# Macropad.net
KiCad netlist of a schematic drawn in EAGLE
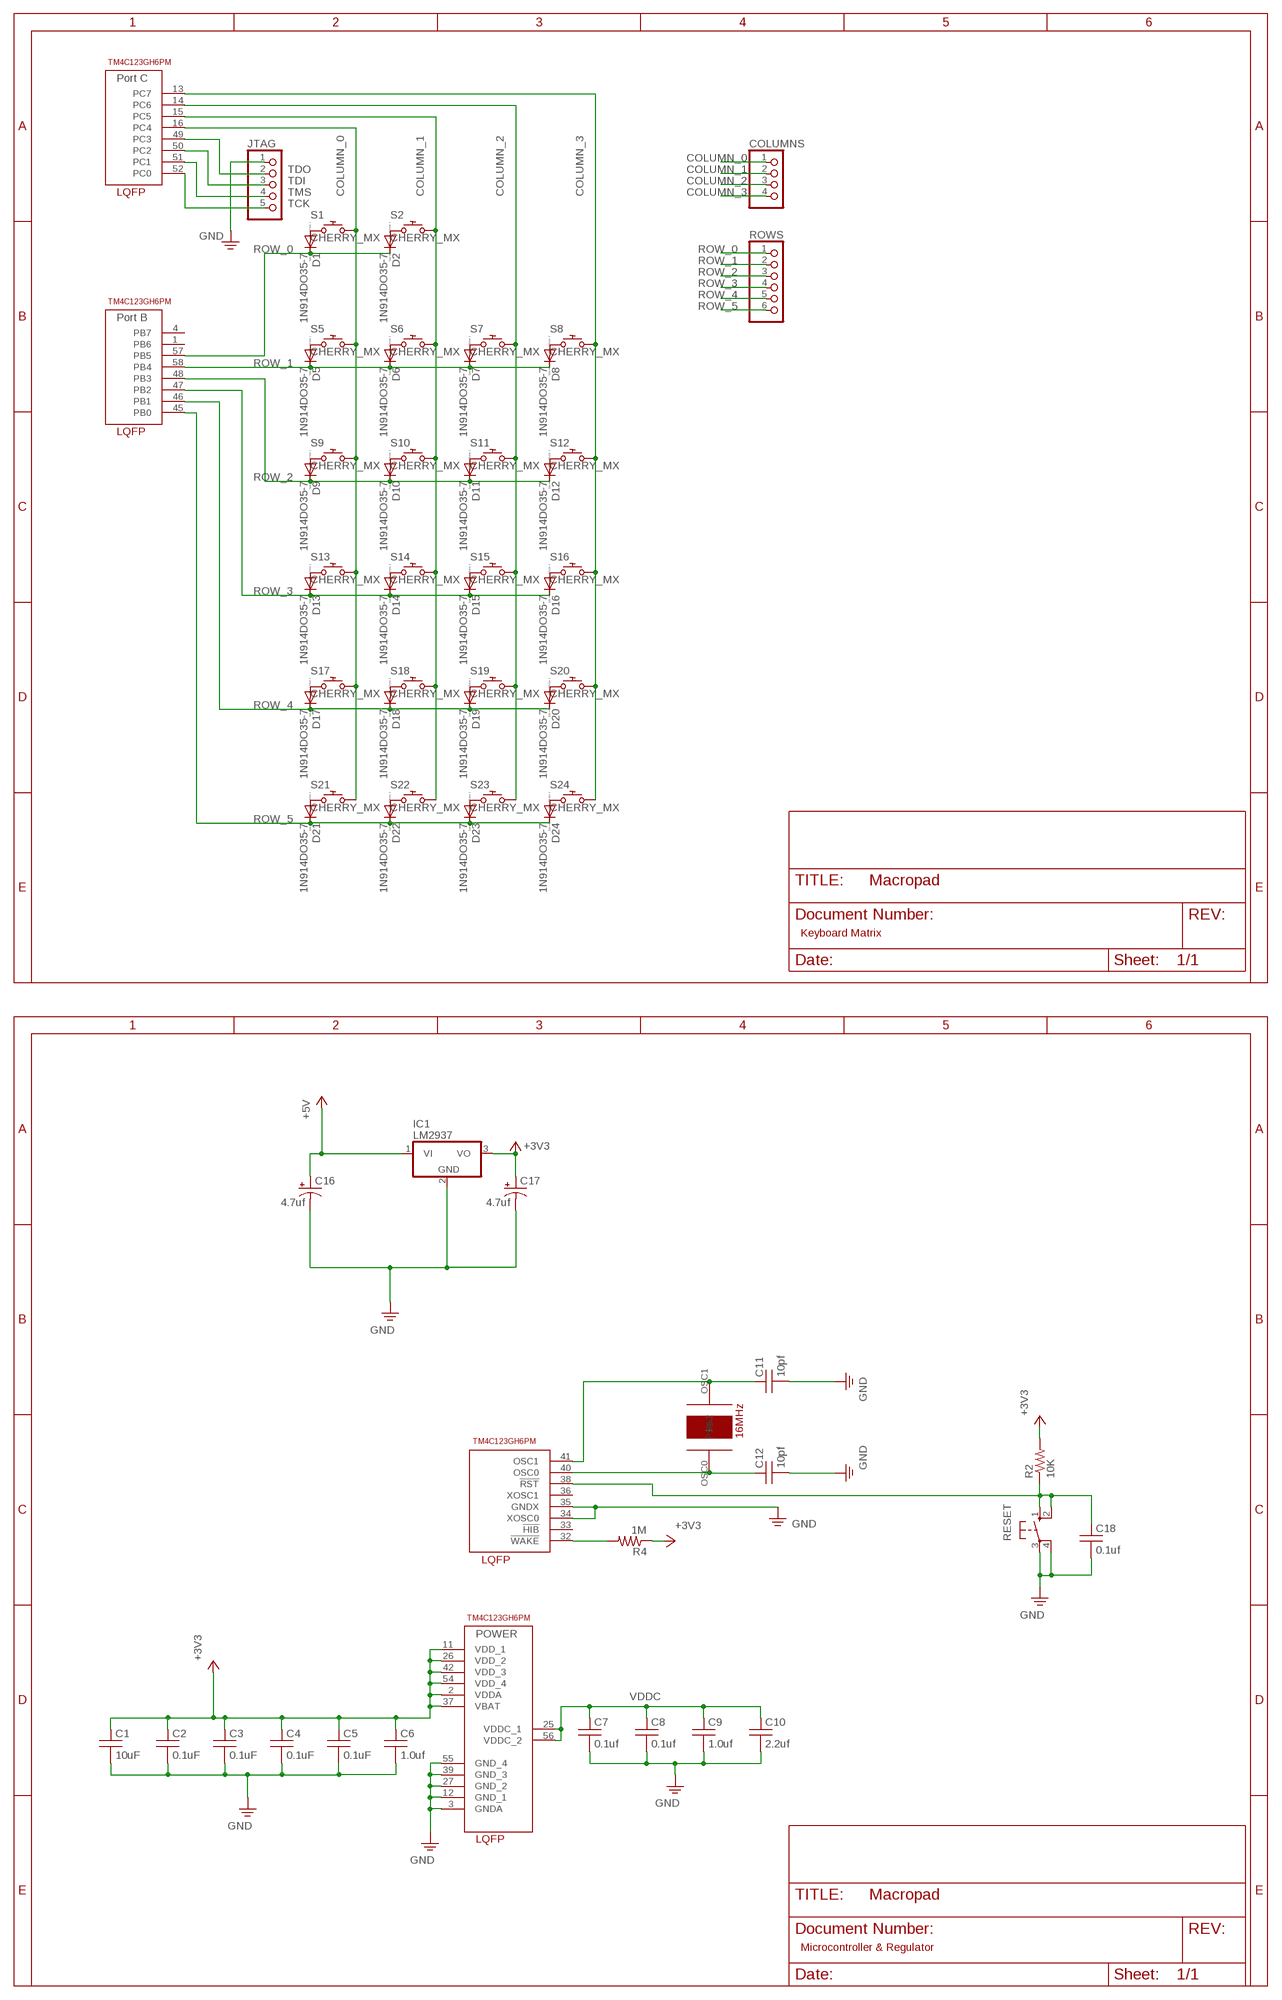
[diagram p0: schematic, sheet 1, part 1 of 2]
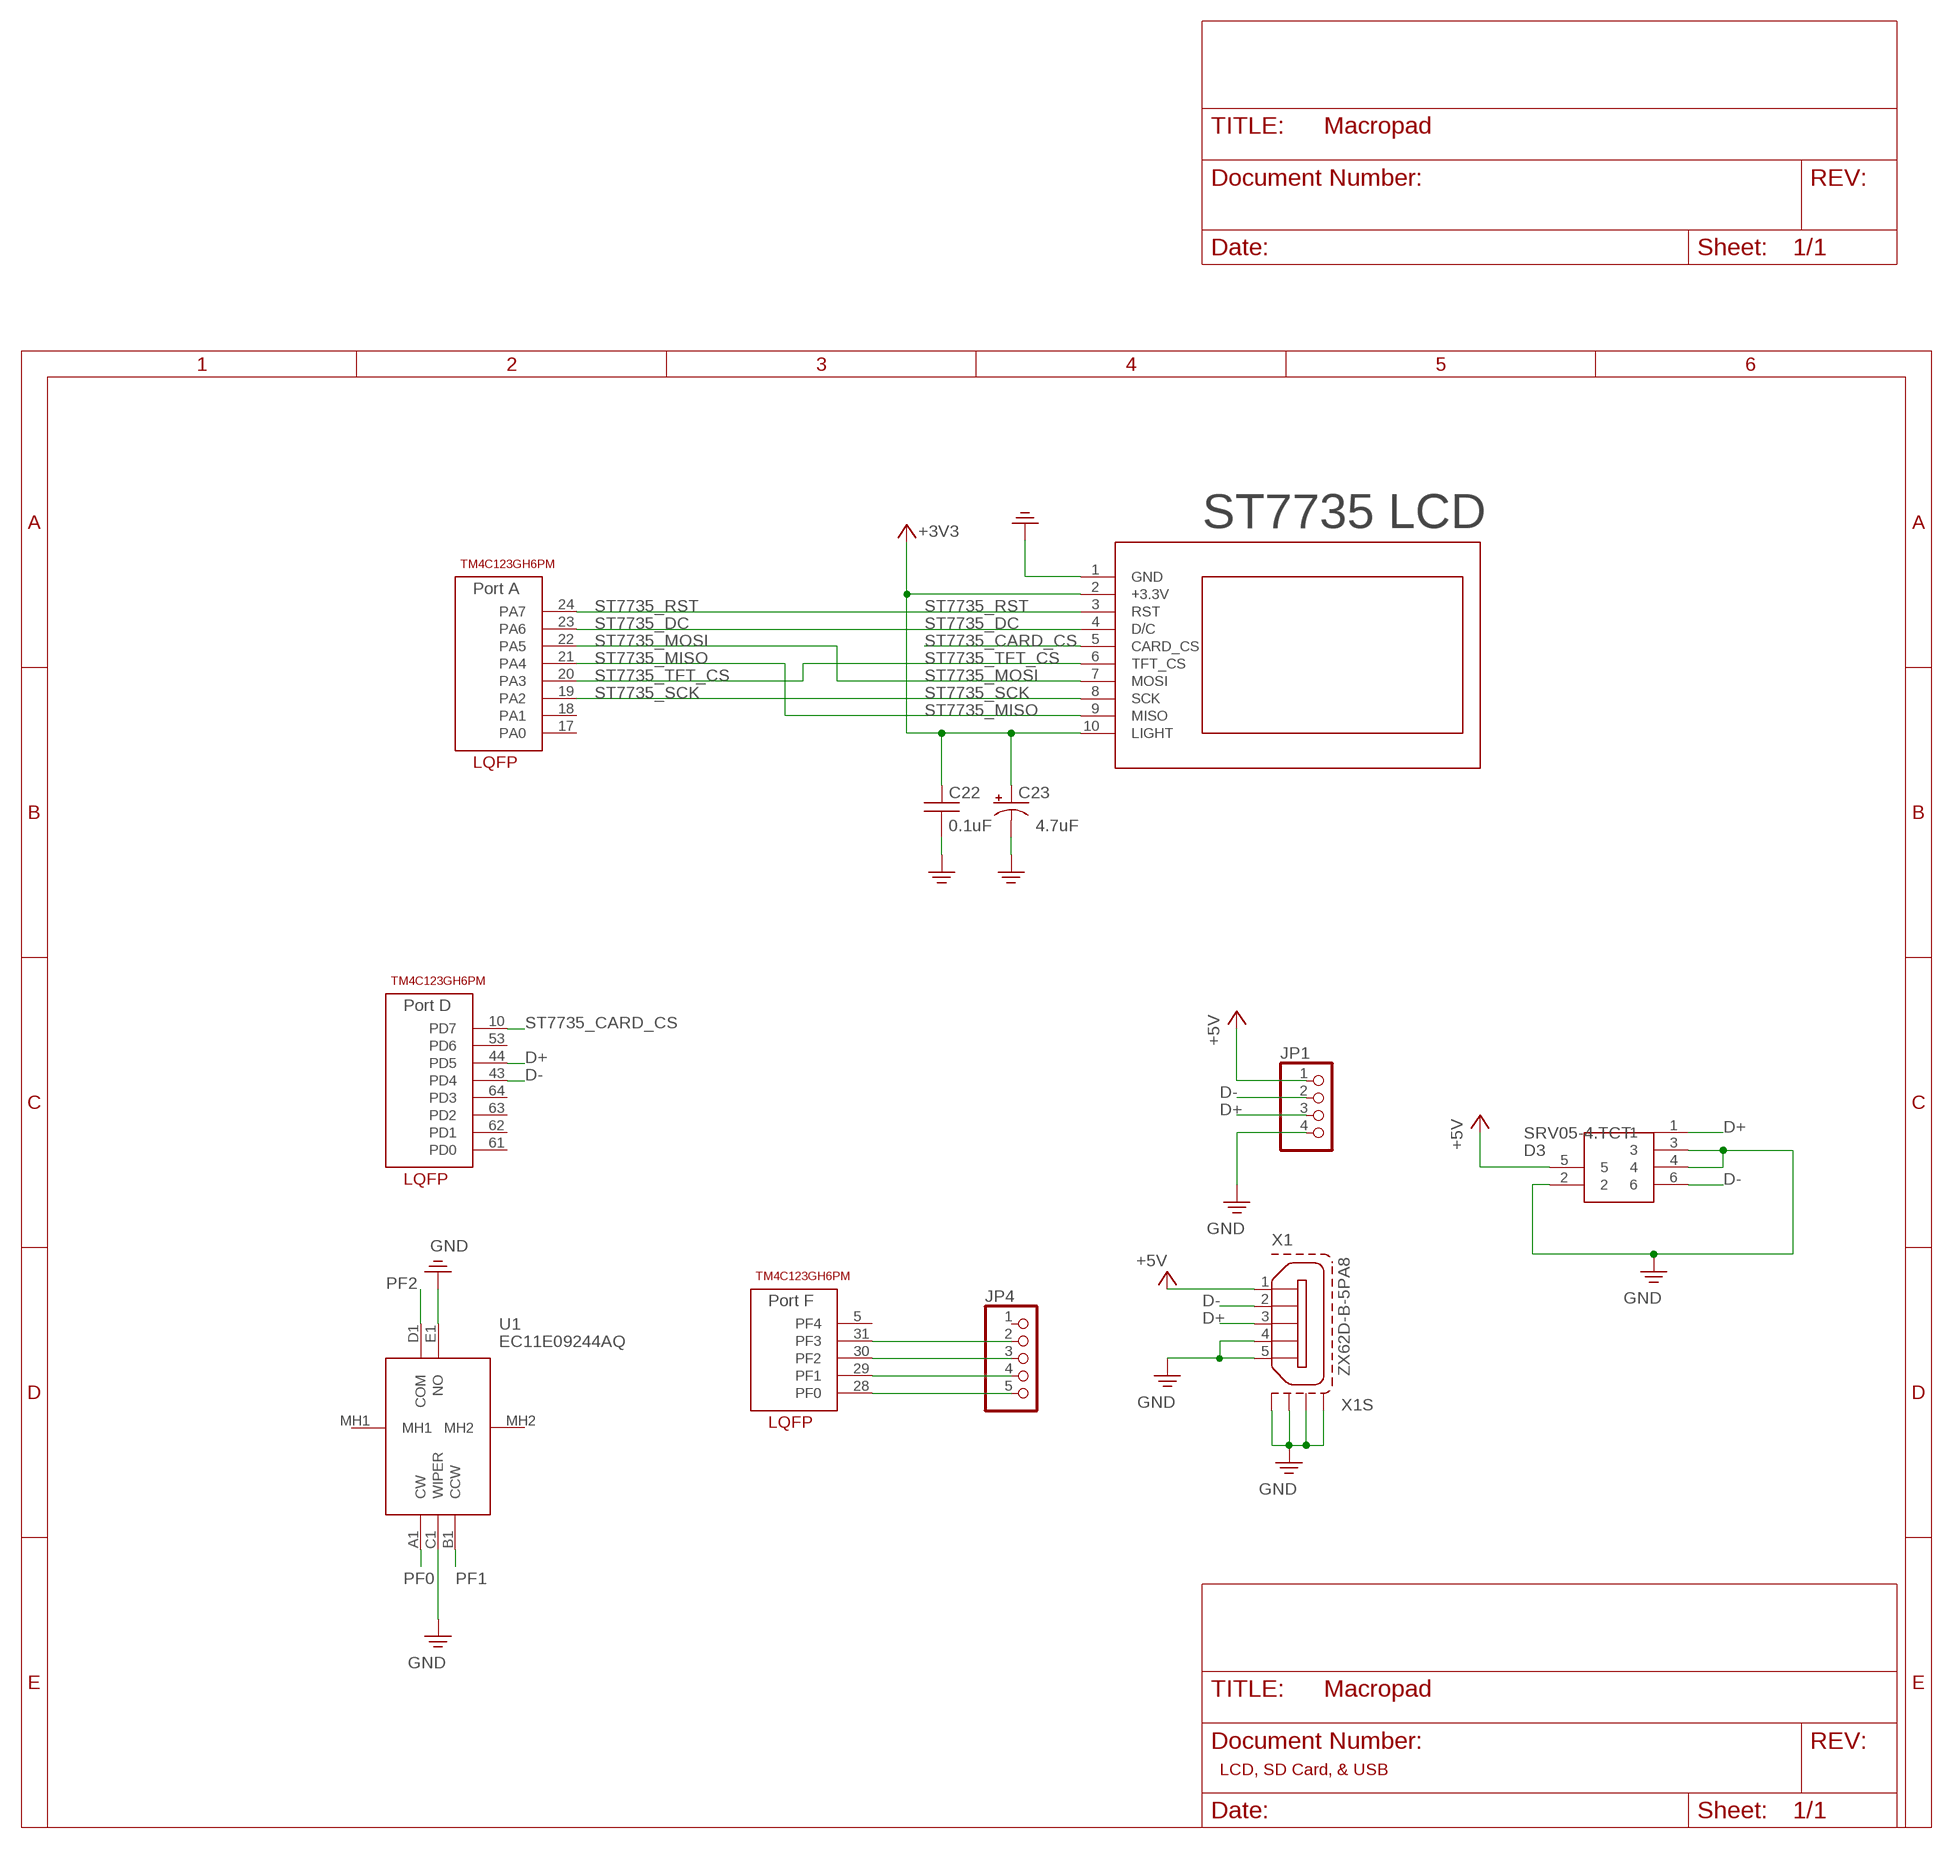
[diagram p1: schematic, sheet 1, part 2 of 2]

(export (version "E")
  (design (tool "Eeschema 10.0.6"))
  (components
    (comp (ref "C1")
      (value "10uF")
      (footprint "eagle-import:CAP100MIL")
      (libsource (lib "eagle-import") (part "CAPACITOR025-024X044"))
    )
    (comp (ref "C2")
      (value "0.1uF")
      (footprint "eagle-import:CAP100MIL")
      (libsource (lib "eagle-import") (part "CAPACITOR025-024X044"))
    )
    (comp (ref "C3")
      (value "0.1uF")
      (footprint "eagle-import:CAP100MIL")
      (libsource (lib "eagle-import") (part "CAPACITOR025-024X044"))
    )
    (comp (ref "C4")
      (value "0.1uF")
      (footprint "eagle-import:CAP100MIL")
      (libsource (lib "eagle-import") (part "CAPACITOR025-024X044"))
    )
    (comp (ref "C5")
      (value "0.1uF")
      (footprint "eagle-import:CAP100MIL")
      (libsource (lib "eagle-import") (part "CAPACITOR025-024X044"))
    )
    (comp (ref "C6")
      (value "1.0uf")
      (footprint "eagle-import:CAP100MIL")
      (libsource (lib "eagle-import") (part "CAPACITOR025-024X044"))
    )
    (comp (ref "C7")
      (value "0.1uf")
      (footprint "eagle-import:CAP100MIL")
      (libsource (lib "eagle-import") (part "CAPACITOR025-024X044"))
    )
    (comp (ref "C8")
      (value "0.1uf")
      (footprint "eagle-import:CAP100MIL")
      (libsource (lib "eagle-import") (part "CAPACITOR025-024X044"))
    )
    (comp (ref "C9")
      (value "1.0uf")
      (footprint "eagle-import:CAP100MIL")
      (libsource (lib "eagle-import") (part "CAPACITOR025-024X044"))
    )
    (comp (ref "C10")
      (value "2.2uf")
      (footprint "eagle-import:CAP100MIL")
      (libsource (lib "eagle-import") (part "CAPACITOR025-024X044"))
    )
    (comp (ref "C11")
      (value "10pf")
      (footprint "eagle-import:CAP100MIL")
      (libsource (lib "eagle-import") (part "CAPACITOR025-024X044"))
    )
    (comp (ref "C12")
      (value "10pf")
      (footprint "eagle-import:CAP100MIL")
      (libsource (lib "eagle-import") (part "CAPACITOR025-024X044"))
    )
    (comp (ref "C16")
      (value "4.7uf")
      (footprint "eagle-import:CAP200MILPOLARIZED")
      (libsource (lib "eagle-import") (part "CAPACITOR_POLARIZEDE5-6"))
    )
    (comp (ref "C17")
      (value "4.7uf")
      (footprint "eagle-import:CAP200MILPOLARIZED")
      (libsource (lib "eagle-import") (part "CAPACITOR_POLARIZEDE5-6"))
    )
    (comp (ref "C18")
      (value "0.1uf")
      (footprint "eagle-import:CAP100MIL")
      (libsource (lib "eagle-import") (part "CAPACITOR025-024X044"))
    )
    (comp (ref "C22")
      (value "0.1uF")
      (footprint "eagle-import:CAP200MIL")
      (libsource (lib "eagle-import") (part "CAPACITOR050-024X044"))
    )
    (comp (ref "C23")
      (value "4.7uF")
      (footprint "eagle-import:CAP200MILPOLARIZED")
      (libsource (lib "eagle-import") (part "CAPACITOR_POLARIZEDE5-6"))
    )
    (comp (ref "COLUMNS")
      (value "PINHD-1X4")
      (footprint "eagle-import:1X04")
      (libsource (lib "eagle-import") (part "PINHD-1X4"))
    )
    (comp (ref "D1")
      (value "1N914DO35-7")
      (footprint "eagle-import:DO35-7")
      (libsource (lib "eagle-import") (part "1N914DO35-7"))
    )
    (comp (ref "D2")
      (value "1N914DO35-7")
      (footprint "eagle-import:DO35-7")
      (libsource (lib "eagle-import") (part "1N914DO35-7"))
    )
    (comp (ref "D3")
      (value "SRV05-4.TCT")
      (footprint "eagle-import:SOT95P280X145-6N")
      (fields (field (name "MF") "Semtech"))
      (libsource (lib "eagle-import") (part "SRV05-4.TCT"))
    )
    (comp (ref "D5")
      (value "1N914DO35-7")
      (footprint "eagle-import:DO35-7")
      (libsource (lib "eagle-import") (part "1N914DO35-7"))
    )
    (comp (ref "D6")
      (value "1N914DO35-7")
      (footprint "eagle-import:DO35-7")
      (libsource (lib "eagle-import") (part "1N914DO35-7"))
    )
    (comp (ref "D7")
      (value "1N914DO35-7")
      (footprint "eagle-import:DO35-7")
      (libsource (lib "eagle-import") (part "1N914DO35-7"))
    )
    (comp (ref "D8")
      (value "1N914DO35-7")
      (footprint "eagle-import:DO35-7")
      (libsource (lib "eagle-import") (part "1N914DO35-7"))
    )
    (comp (ref "D9")
      (value "1N914DO35-7")
      (footprint "eagle-import:DO35-7")
      (libsource (lib "eagle-import") (part "1N914DO35-7"))
    )
    (comp (ref "D10")
      (value "1N914DO35-7")
      (footprint "eagle-import:DO35-7")
      (libsource (lib "eagle-import") (part "1N914DO35-7"))
    )
    (comp (ref "D11")
      (value "1N914DO35-7")
      (footprint "eagle-import:DO35-7")
      (libsource (lib "eagle-import") (part "1N914DO35-7"))
    )
    (comp (ref "D12")
      (value "1N914DO35-7")
      (footprint "eagle-import:DO35-7")
      (libsource (lib "eagle-import") (part "1N914DO35-7"))
    )
    (comp (ref "D13")
      (value "1N914DO35-7")
      (footprint "eagle-import:DO35-7")
      (libsource (lib "eagle-import") (part "1N914DO35-7"))
    )
    (comp (ref "D14")
      (value "1N914DO35-7")
      (footprint "eagle-import:DO35-7")
      (libsource (lib "eagle-import") (part "1N914DO35-7"))
    )
    (comp (ref "D15")
      (value "1N914DO35-7")
      (footprint "eagle-import:DO35-7")
      (libsource (lib "eagle-import") (part "1N914DO35-7"))
    )
    (comp (ref "D16")
      (value "1N914DO35-7")
      (footprint "eagle-import:DO35-7")
      (libsource (lib "eagle-import") (part "1N914DO35-7"))
    )
    (comp (ref "D17")
      (value "1N914DO35-7")
      (footprint "eagle-import:DO35-7")
      (libsource (lib "eagle-import") (part "1N914DO35-7"))
    )
    (comp (ref "D18")
      (value "1N914DO35-7")
      (footprint "eagle-import:DO35-7")
      (libsource (lib "eagle-import") (part "1N914DO35-7"))
    )
    (comp (ref "D19")
      (value "1N914DO35-7")
      (footprint "eagle-import:DO35-7")
      (libsource (lib "eagle-import") (part "1N914DO35-7"))
    )
    (comp (ref "D20")
      (value "1N914DO35-7")
      (footprint "eagle-import:DO35-7")
      (libsource (lib "eagle-import") (part "1N914DO35-7"))
    )
    (comp (ref "D21")
      (value "1N914DO35-7")
      (footprint "eagle-import:DO35-7")
      (libsource (lib "eagle-import") (part "1N914DO35-7"))
    )
    (comp (ref "D22")
      (value "1N914DO35-7")
      (footprint "eagle-import:DO35-7")
      (libsource (lib "eagle-import") (part "1N914DO35-7"))
    )
    (comp (ref "D23")
      (value "1N914DO35-7")
      (footprint "eagle-import:DO35-7")
      (libsource (lib "eagle-import") (part "1N914DO35-7"))
    )
    (comp (ref "D24")
      (value "1N914DO35-7")
      (footprint "eagle-import:DO35-7")
      (libsource (lib "eagle-import") (part "1N914DO35-7"))
    )
    (comp (ref "IC1")
      (value "LM2937")
      (footprint "eagle-import:TO220")
      (libsource (lib "eagle-import") (part "LM2937"))
    )
    (comp (ref "JP1")
      (value "PINHD-1X4")
      (footprint "eagle-import:1X04")
      (libsource (lib "eagle-import") (part "PINHD-1X4"))
    )
    (comp (ref "JP4")
      (value "PINHD-1X5")
      (footprint "eagle-import:1X05")
      (libsource (lib "eagle-import") (part "PINHD-1X5"))
    )
    (comp (ref "JTAG")
      (value "PINHD-1X5")
      (footprint "eagle-import:1X05")
      (libsource (lib "eagle-import") (part "PINHD-1X5"))
    )
    (comp (ref "R2")
      (value "10K")
      (footprint "eagle-import:RES200MIL")
      (libsource (lib "eagle-import") (part "RESISTOR0204/5"))
    )
    (comp (ref "R4")
      (value "1M")
      (footprint "eagle-import:RES200MIL")
      (libsource (lib "eagle-import") (part "RESISTOR0204/5"))
    )
    (comp (ref "RESET")
      (value "B3F-1052")
      (footprint "eagle-import:B3F-10XX")
      (fields (field (name "MPN") "B3F-1000"))
      (libsource (lib "eagle-import") (part "B3F-1052"))
    )
    (comp (ref "ROWS")
      (value "PINHD-1X6")
      (footprint "eagle-import:1X06")
      (libsource (lib "eagle-import") (part "PINHD-1X6"))
    )
    (comp (ref "S1")
      (value "CHERRY_MX")
      (footprint "eagle-import:CHERRY_MX")
      (libsource (lib "eagle-import") (part "CHERRY_MX"))
    )
    (comp (ref "S2")
      (value "CHERRY_MX")
      (footprint "eagle-import:CHERRY_MX")
      (libsource (lib "eagle-import") (part "CHERRY_MX"))
    )
    (comp (ref "S5")
      (value "CHERRY_MX")
      (footprint "eagle-import:CHERRY_MX")
      (libsource (lib "eagle-import") (part "CHERRY_MX"))
    )
    (comp (ref "S6")
      (value "CHERRY_MX")
      (footprint "eagle-import:CHERRY_MX")
      (libsource (lib "eagle-import") (part "CHERRY_MX"))
    )
    (comp (ref "S7")
      (value "CHERRY_MX")
      (footprint "eagle-import:CHERRY_MX")
      (libsource (lib "eagle-import") (part "CHERRY_MX"))
    )
    (comp (ref "S8")
      (value "CHERRY_MX")
      (footprint "eagle-import:CHERRY_MX")
      (libsource (lib "eagle-import") (part "CHERRY_MX"))
    )
    (comp (ref "S9")
      (value "CHERRY_MX")
      (footprint "eagle-import:CHERRY_MX")
      (libsource (lib "eagle-import") (part "CHERRY_MX"))
    )
    (comp (ref "S10")
      (value "CHERRY_MX")
      (footprint "eagle-import:CHERRY_MX")
      (libsource (lib "eagle-import") (part "CHERRY_MX"))
    )
    (comp (ref "S11")
      (value "CHERRY_MX")
      (footprint "eagle-import:CHERRY_MX")
      (libsource (lib "eagle-import") (part "CHERRY_MX"))
    )
    (comp (ref "S12")
      (value "CHERRY_MX")
      (footprint "eagle-import:CHERRY_MX")
      (libsource (lib "eagle-import") (part "CHERRY_MX"))
    )
    (comp (ref "S13")
      (value "CHERRY_MX")
      (footprint "eagle-import:CHERRY_MX")
      (libsource (lib "eagle-import") (part "CHERRY_MX"))
    )
    (comp (ref "S14")
      (value "CHERRY_MX")
      (footprint "eagle-import:CHERRY_MX")
      (libsource (lib "eagle-import") (part "CHERRY_MX"))
    )
    (comp (ref "S15")
      (value "CHERRY_MX")
      (footprint "eagle-import:CHERRY_MX")
      (libsource (lib "eagle-import") (part "CHERRY_MX"))
    )
    (comp (ref "S16")
      (value "CHERRY_MX")
      (footprint "eagle-import:CHERRY_MX")
      (libsource (lib "eagle-import") (part "CHERRY_MX"))
    )
    (comp (ref "S17")
      (value "CHERRY_MX")
      (footprint "eagle-import:CHERRY_MX")
      (libsource (lib "eagle-import") (part "CHERRY_MX"))
    )
    (comp (ref "S18")
      (value "CHERRY_MX")
      (footprint "eagle-import:CHERRY_MX")
      (libsource (lib "eagle-import") (part "CHERRY_MX"))
    )
    (comp (ref "S19")
      (value "CHERRY_MX")
      (footprint "eagle-import:CHERRY_MX")
      (libsource (lib "eagle-import") (part "CHERRY_MX"))
    )
    (comp (ref "S20")
      (value "CHERRY_MX")
      (footprint "eagle-import:CHERRY_MX")
      (libsource (lib "eagle-import") (part "CHERRY_MX"))
    )
    (comp (ref "S21")
      (value "CHERRY_MX")
      (footprint "eagle-import:CHERRY_MX")
      (libsource (lib "eagle-import") (part "CHERRY_MX"))
    )
    (comp (ref "S22")
      (value "CHERRY_MX")
      (footprint "eagle-import:CHERRY_MX")
      (libsource (lib "eagle-import") (part "CHERRY_MX"))
    )
    (comp (ref "S23")
      (value "CHERRY_MX")
      (footprint "eagle-import:CHERRY_MX")
      (libsource (lib "eagle-import") (part "CHERRY_MX"))
    )
    (comp (ref "S24")
      (value "CHERRY_MX")
      (footprint "eagle-import:CHERRY_MX")
      (libsource (lib "eagle-import") (part "CHERRY_MX"))
    )
    (comp (ref "U$1")
      (value "TM4C123GH6PM")
      (footprint "eagle-import:QFP50P1200X1200X160-64N")
      (libsource (lib "eagle-import") (part "TM4C123GH6PM"))
    )
    (comp (ref "U$2")
      (value "16MHZ_CRYSTAL")
      (footprint "eagle-import:16MHZ_CRYSTAL")
      (libsource (lib "eagle-import") (part "16MHZ_CRYSTAL"))
    )
    (comp (ref "U$6")
      (value "ST7735")
      (footprint "eagle-import:ST7735")
      (libsource (lib "eagle-import") (part "ST7735"))
    )
    (comp (ref "U1")
      (value "EC11E09244AQ")
      (footprint "eagle-import:EC11E09244AQ")
      (fields (field (name "MOUSER_PART_NUMBER") "688-EC11E09244AQ"))
      (libsource (lib "eagle-import") (part "EC11E09244AQ"))
    )
    (comp (ref "X1")
      (value "ZX62D-B-5PA8")
      (footprint "eagle-import:ZX62D-B-5PA8")
      (fields (field (name "MF") "Hirose"))
      (libsource (lib "eagle-import") (part "ZX62D-B-5PA8"))
    )
  )
  (nets
    (net (code "1") (name "+3V3") (class "Default")
      (node (ref "C1") (pin "1") (pinfunction "1_1") (pintype "passive"))
      (node (ref "C17") (pin "+") (pinfunction "+_+") (pintype "passive"))
      (node (ref "C2") (pin "1") (pinfunction "1_1") (pintype "passive"))
      (node (ref "C22") (pin "1") (pinfunction "1_1") (pintype "passive"))
      (node (ref "C23") (pin "+") (pinfunction "+_+") (pintype "passive"))
      (node (ref "C3") (pin "1") (pinfunction "1_1") (pintype "passive"))
      (node (ref "C4") (pin "1") (pinfunction "1_1") (pintype "passive"))
      (node (ref "C5") (pin "1") (pinfunction "1_1") (pintype "passive"))
      (node (ref "C6") (pin "1") (pinfunction "1_1") (pintype "passive"))
      (node (ref "IC1") (pin "3") (pinfunction "VO_3") (pintype "passive"))
      (node (ref "R2") (pin "2") (pinfunction "2_2") (pintype "passive"))
      (node (ref "R4") (pin "1") (pinfunction "1_1") (pintype "passive"))
      (node (ref "U$1") (pin "11") (pinfunction "VDD_1_11") (pintype "bidirectional"))
      (node (ref "U$1") (pin "2") (pinfunction "VDDA_2") (pintype "bidirectional"))
      (node (ref "U$1") (pin "26") (pinfunction "VDD_2_26") (pintype "bidirectional"))
      (node (ref "U$1") (pin "37") (pinfunction "VBAT_37") (pintype "bidirectional"))
      (node (ref "U$1") (pin "42") (pinfunction "VDD_3_42") (pintype "bidirectional"))
      (node (ref "U$1") (pin "54") (pinfunction "VDD_4_54") (pintype "bidirectional"))
      (node (ref "U$6") (pin "10") (pinfunction "LIGHT_10") (pintype "bidirectional"))
      (node (ref "U$6") (pin "2") (pinfunction "+3.3V_2") (pintype "bidirectional"))
    )
    (net (code "2") (name "+5V") (class "Default")
      (node (ref "C16") (pin "+") (pinfunction "+_+") (pintype "passive"))
      (node (ref "D3") (pin "5") (pinfunction "5_5") (pintype "bidirectional"))
      (node (ref "IC1") (pin "1") (pinfunction "VI_1") (pintype "input"))
      (node (ref "JP1") (pin "1") (pinfunction "1_1") (pintype "passive"))
      (node (ref "X1") (pin "1") (pinfunction "1_1") (pintype "passive"))
    )
    (net (code "3") (name "/COLUMN_0") (class "Default")
      (node (ref "COLUMNS") (pin "1") (pinfunction "1_1") (pintype "passive"))
      (node (ref "S1") (pin "S2") (pinfunction "2_S2") (pintype "passive"))
      (node (ref "S13") (pin "S2") (pinfunction "2_S2") (pintype "passive"))
      (node (ref "S17") (pin "S2") (pinfunction "2_S2") (pintype "passive"))
      (node (ref "S21") (pin "S2") (pinfunction "2_S2") (pintype "passive"))
      (node (ref "S5") (pin "S2") (pinfunction "2_S2") (pintype "passive"))
      (node (ref "S9") (pin "S2") (pinfunction "2_S2") (pintype "passive"))
      (node (ref "U$1") (pin "16") (pinfunction "PC4_16") (pintype "bidirectional"))
    )
    (net (code "4") (name "/COLUMN_1") (class "Default")
      (node (ref "COLUMNS") (pin "2") (pinfunction "2_2") (pintype "passive"))
      (node (ref "S10") (pin "S2") (pinfunction "2_S2") (pintype "passive"))
      (node (ref "S14") (pin "S2") (pinfunction "2_S2") (pintype "passive"))
      (node (ref "S18") (pin "S2") (pinfunction "2_S2") (pintype "passive"))
      (node (ref "S2") (pin "S2") (pinfunction "2_S2") (pintype "passive"))
      (node (ref "S22") (pin "S2") (pinfunction "2_S2") (pintype "passive"))
      (node (ref "S6") (pin "S2") (pinfunction "2_S2") (pintype "passive"))
      (node (ref "U$1") (pin "15") (pinfunction "PC5_15") (pintype "bidirectional"))
    )
    (net (code "5") (name "/COLUMN_2") (class "Default")
      (node (ref "COLUMNS") (pin "3") (pinfunction "3_3") (pintype "passive"))
      (node (ref "S11") (pin "S2") (pinfunction "2_S2") (pintype "passive"))
      (node (ref "S15") (pin "S2") (pinfunction "2_S2") (pintype "passive"))
      (node (ref "S19") (pin "S2") (pinfunction "2_S2") (pintype "passive"))
      (node (ref "S23") (pin "S2") (pinfunction "2_S2") (pintype "passive"))
      (node (ref "S7") (pin "S2") (pinfunction "2_S2") (pintype "passive"))
      (node (ref "U$1") (pin "14") (pinfunction "PC6_14") (pintype "bidirectional"))
    )
    (net (code "6") (name "/COLUMN_3") (class "Default")
      (node (ref "COLUMNS") (pin "4") (pinfunction "4_4") (pintype "passive"))
      (node (ref "S12") (pin "S2") (pinfunction "2_S2") (pintype "passive"))
      (node (ref "S16") (pin "S2") (pinfunction "2_S2") (pintype "passive"))
      (node (ref "S20") (pin "S2") (pinfunction "2_S2") (pintype "passive"))
      (node (ref "S24") (pin "S2") (pinfunction "2_S2") (pintype "passive"))
      (node (ref "S8") (pin "S2") (pinfunction "2_S2") (pintype "passive"))
      (node (ref "U$1") (pin "13") (pinfunction "PC7_13") (pintype "bidirectional"))
    )
    (net (code "7") (name "/D+") (class "Default")
      (node (ref "D3") (pin "1") (pinfunction "1_1") (pintype "bidirectional"))
      (node (ref "JP1") (pin "3") (pinfunction "3_3") (pintype "passive"))
      (node (ref "U$1") (pin "44") (pinfunction "PD5_44") (pintype "bidirectional"))
      (node (ref "X1") (pin "3") (pinfunction "3_3") (pintype "passive"))
    )
    (net (code "8") (name "/D-") (class "Default")
      (node (ref "D3") (pin "6") (pinfunction "6_6") (pintype "bidirectional"))
      (node (ref "JP1") (pin "2") (pinfunction "2_2") (pintype "passive"))
      (node (ref "U$1") (pin "43") (pinfunction "PD4_43") (pintype "bidirectional"))
      (node (ref "X1") (pin "2") (pinfunction "2_2") (pintype "passive"))
    )
    (net (code "9") (name "/PF0") (class "Default")
      (node (ref "JP4") (pin "5") (pinfunction "5_5") (pintype "passive"))
      (node (ref "U$1") (pin "28") (pinfunction "PF0_28") (pintype "bidirectional"))
      (node (ref "U1") (pin "A1") (pinfunction "CW_A1") (pintype "bidirectional"))
    )
    (net (code "10") (name "/PF1") (class "Default")
      (node (ref "JP4") (pin "4") (pinfunction "4_4") (pintype "passive"))
      (node (ref "U$1") (pin "29") (pinfunction "PF1_29") (pintype "bidirectional"))
      (node (ref "U1") (pin "B1") (pinfunction "CCW_B1") (pintype "bidirectional"))
    )
    (net (code "11") (name "/PF2") (class "Default")
      (node (ref "JP4") (pin "3") (pinfunction "3_3") (pintype "passive"))
      (node (ref "U$1") (pin "30") (pinfunction "PF2_30") (pintype "bidirectional"))
      (node (ref "U1") (pin "D1") (pinfunction "COM_D1") (pintype "bidirectional"))
    )
    (net (code "12") (name "/ROW_0") (class "Default")
      (node (ref "D1") (pin "C") (pinfunction "C_C") (pintype "passive"))
      (node (ref "D2") (pin "C") (pinfunction "C_C") (pintype "passive"))
      (node (ref "ROWS") (pin "1") (pinfunction "1_1") (pintype "passive"))
      (node (ref "U$1") (pin "57") (pinfunction "PB5_57") (pintype "bidirectional"))
    )
    (net (code "13") (name "/ROW_1") (class "Default")
      (node (ref "D5") (pin "C") (pinfunction "C_C") (pintype "passive"))
      (node (ref "D6") (pin "C") (pinfunction "C_C") (pintype "passive"))
      (node (ref "D7") (pin "C") (pinfunction "C_C") (pintype "passive"))
      (node (ref "D8") (pin "C") (pinfunction "C_C") (pintype "passive"))
      (node (ref "ROWS") (pin "2") (pinfunction "2_2") (pintype "passive"))
      (node (ref "U$1") (pin "58") (pinfunction "PB4_58") (pintype "bidirectional"))
    )
    (net (code "14") (name "/ROW_2") (class "Default")
      (node (ref "D10") (pin "C") (pinfunction "C_C") (pintype "passive"))
      (node (ref "D11") (pin "C") (pinfunction "C_C") (pintype "passive"))
      (node (ref "D12") (pin "C") (pinfunction "C_C") (pintype "passive"))
      (node (ref "D9") (pin "C") (pinfunction "C_C") (pintype "passive"))
      (node (ref "ROWS") (pin "3") (pinfunction "3_3") (pintype "passive"))
      (node (ref "U$1") (pin "48") (pinfunction "PB3_48") (pintype "bidirectional"))
    )
    (net (code "15") (name "/ROW_3") (class "Default")
      (node (ref "D13") (pin "C") (pinfunction "C_C") (pintype "passive"))
      (node (ref "D14") (pin "C") (pinfunction "C_C") (pintype "passive"))
      (node (ref "D15") (pin "C") (pinfunction "C_C") (pintype "passive"))
      (node (ref "D16") (pin "C") (pinfunction "C_C") (pintype "passive"))
      (node (ref "ROWS") (pin "4") (pinfunction "4_4") (pintype "passive"))
      (node (ref "U$1") (pin "47") (pinfunction "PB2_47") (pintype "bidirectional"))
    )
    (net (code "16") (name "/ROW_4") (class "Default")
      (node (ref "D17") (pin "C") (pinfunction "C_C") (pintype "passive"))
      (node (ref "D18") (pin "C") (pinfunction "C_C") (pintype "passive"))
      (node (ref "D19") (pin "C") (pinfunction "C_C") (pintype "passive"))
      (node (ref "D20") (pin "C") (pinfunction "C_C") (pintype "passive"))
      (node (ref "ROWS") (pin "5") (pinfunction "5_5") (pintype "passive"))
      (node (ref "U$1") (pin "46") (pinfunction "PB1_46") (pintype "bidirectional"))
    )
    (net (code "17") (name "/ROW_5") (class "Default")
      (node (ref "D21") (pin "C") (pinfunction "C_C") (pintype "passive"))
      (node (ref "D22") (pin "C") (pinfunction "C_C") (pintype "passive"))
      (node (ref "D23") (pin "C") (pinfunction "C_C") (pintype "passive"))
      (node (ref "D24") (pin "C") (pinfunction "C_C") (pintype "passive"))
      (node (ref "ROWS") (pin "6") (pinfunction "6_6") (pintype "passive"))
      (node (ref "U$1") (pin "45") (pinfunction "PB0_45") (pintype "bidirectional"))
    )
    (net (code "18") (name "/ST7735_CARD_CS") (class "Default")
      (node (ref "U$1") (pin "10") (pinfunction "PD7_10") (pintype "bidirectional"))
      (node (ref "U$6") (pin "5") (pinfunction "CARD_CS_5") (pintype "bidirectional"))
    )
    (net (code "19") (name "/ST7735_DC") (class "Default")
      (node (ref "U$1") (pin "23") (pinfunction "PA6_23") (pintype "bidirectional"))
      (node (ref "U$6") (pin "4") (pinfunction "D/C_4") (pintype "bidirectional"))
    )
    (net (code "20") (name "/ST7735_MISO") (class "Default")
      (node (ref "U$1") (pin "21") (pinfunction "PA4_21") (pintype "bidirectional"))
      (node (ref "U$6") (pin "9") (pinfunction "MISO_9") (pintype "bidirectional"))
    )
    (net (code "21") (name "/ST7735_MOSI") (class "Default")
      (node (ref "U$1") (pin "22") (pinfunction "PA5_22") (pintype "bidirectional"))
      (node (ref "U$6") (pin "7") (pinfunction "MOSI_7") (pintype "bidirectional"))
    )
    (net (code "22") (name "/ST7735_RST") (class "Default")
      (node (ref "U$1") (pin "24") (pinfunction "PA7_24") (pintype "bidirectional"))
      (node (ref "U$6") (pin "3") (pinfunction "RST_3") (pintype "bidirectional"))
    )
    (net (code "23") (name "/ST7735_SCK") (class "Default")
      (node (ref "U$1") (pin "19") (pinfunction "PA2_19") (pintype "bidirectional"))
      (node (ref "U$6") (pin "8") (pinfunction "SCK_8") (pintype "bidirectional"))
    )
    (net (code "24") (name "/ST7735_TFT_CS") (class "Default")
      (node (ref "U$1") (pin "20") (pinfunction "PA3_20") (pintype "bidirectional"))
      (node (ref "U$6") (pin "6") (pinfunction "TFT_CS_6") (pintype "bidirectional"))
    )
    (net (code "25") (name "/TCK") (class "Default")
      (node (ref "JTAG") (pin "5") (pinfunction "5_5") (pintype "passive"))
      (node (ref "U$1") (pin "52") (pinfunction "PC0_52") (pintype "bidirectional"))
    )
    (net (code "26") (name "/TDI") (class "Default")
      (node (ref "JTAG") (pin "3") (pinfunction "3_3") (pintype "passive"))
      (node (ref "U$1") (pin "50") (pinfunction "PC2_50") (pintype "bidirectional"))
    )
    (net (code "27") (name "/TDO") (class "Default")
      (node (ref "JTAG") (pin "2") (pinfunction "2_2") (pintype "passive"))
      (node (ref "U$1") (pin "49") (pinfunction "PC3_49") (pintype "bidirectional"))
    )
    (net (code "28") (name "/TMS") (class "Default")
      (node (ref "JTAG") (pin "4") (pinfunction "4_4") (pintype "passive"))
      (node (ref "U$1") (pin "51") (pinfunction "PC1_51") (pintype "bidirectional"))
    )
    (net (code "29") (name "/VDDC") (class "Default")
      (node (ref "C10") (pin "1") (pinfunction "1_1") (pintype "passive"))
      (node (ref "C7") (pin "1") (pinfunction "1_1") (pintype "passive"))
      (node (ref "C8") (pin "1") (pinfunction "1_1") (pintype "passive"))
      (node (ref "C9") (pin "1") (pinfunction "1_1") (pintype "passive"))
      (node (ref "U$1") (pin "25") (pinfunction "VDDC_1_25") (pintype "bidirectional"))
      (node (ref "U$1") (pin "56") (pinfunction "VDDC_2_56") (pintype "bidirectional"))
    )
    (net (code "30") (name "GND") (class "Default")
      (node (ref "C1") (pin "2") (pinfunction "2_2") (pintype "passive"))
      (node (ref "C10") (pin "2") (pinfunction "2_2") (pintype "passive"))
      (node (ref "C11") (pin "2") (pinfunction "2_2") (pintype "passive"))
      (node (ref "C12") (pin "2") (pinfunction "2_2") (pintype "passive"))
      (node (ref "C16") (pin "-") (pinfunction "-_-") (pintype "passive"))
      (node (ref "C17") (pin "-") (pinfunction "-_-") (pintype "passive"))
      (node (ref "C18") (pin "2") (pinfunction "2_2") (pintype "passive"))
      (node (ref "C2") (pin "2") (pinfunction "2_2") (pintype "passive"))
      (node (ref "C22") (pin "2") (pinfunction "2_2") (pintype "passive"))
      (node (ref "C23") (pin "-") (pinfunction "-_-") (pintype "passive"))
      (node (ref "C3") (pin "2") (pinfunction "2_2") (pintype "passive"))
      (node (ref "C4") (pin "2") (pinfunction "2_2") (pintype "passive"))
      (node (ref "C5") (pin "2") (pinfunction "2_2") (pintype "passive"))
      (node (ref "C6") (pin "2") (pinfunction "2_2") (pintype "passive"))
      (node (ref "C7") (pin "2") (pinfunction "2_2") (pintype "passive"))
      (node (ref "C8") (pin "2") (pinfunction "2_2") (pintype "passive"))
      (node (ref "C9") (pin "2") (pinfunction "2_2") (pintype "passive"))
      (node (ref "D3") (pin "2") (pinfunction "2_2") (pintype "bidirectional"))
      (node (ref "D3") (pin "3") (pinfunction "3_3") (pintype "bidirectional"))
      (node (ref "D3") (pin "4") (pinfunction "4_4") (pintype "bidirectional"))
      (node (ref "IC1") (pin "2") (pinfunction "GND_2") (pintype "passive"))
      (node (ref "JP1") (pin "4") (pinfunction "4_4") (pintype "passive"))
      (node (ref "JTAG") (pin "1") (pinfunction "1_1") (pintype "passive"))
      (node (ref "RESET") (pin "3") (pinfunction "P_3") (pintype "passive"))
      (node (ref "RESET") (pin "4") (pinfunction "P1_4") (pintype "passive"))
      (node (ref "U$1") (pin "12") (pinfunction "GND_1_12") (pintype "bidirectional"))
      (node (ref "U$1") (pin "27") (pinfunction "GND_2_27") (pintype "bidirectional"))
      (node (ref "U$1") (pin "3") (pinfunction "GNDA_3") (pintype "bidirectional"))
      (node (ref "U$1") (pin "34") (pinfunction "XOSC0_34") (pintype "bidirectional"))
      (node (ref "U$1") (pin "35") (pinfunction "GNDX_35") (pintype "bidirectional"))
      (node (ref "U$1") (pin "39") (pinfunction "GND_3_39") (pintype "bidirectional"))
      (node (ref "U$1") (pin "55") (pinfunction "GND_4_55") (pintype "bidirectional"))
      (node (ref "U$6") (pin "1") (pinfunction "GND_1") (pintype "bidirectional"))
      (node (ref "U1") (pin "C1") (pinfunction "WIPER_C1") (pintype "bidirectional"))
      (node (ref "U1") (pin "E1") (pinfunction "NO_E1") (pintype "bidirectional"))
      (node (ref "X1") (pin "4") (pinfunction "4_4") (pintype "passive"))
      (node (ref "X1") (pin "5") (pinfunction "5_5") (pintype "passive"))
      (node (ref "X1") (pin "S1") (pinfunction "S1_S1") (pintype "passive"))
      (node (ref "X1") (pin "S2") (pinfunction "S2_S2") (pintype "passive"))
      (node (ref "X1") (pin "S3") (pinfunction "S3_S3") (pintype "passive"))
      (node (ref "X1") (pin "S4") (pinfunction "S4_S4") (pintype "passive"))
    )
    (net (code "31") (name "Net-(RESET-S)") (class "Default")
      (node (ref "C18") (pin "1") (pinfunction "1_1") (pintype "passive"))
      (node (ref "R2") (pin "1") (pinfunction "1_1") (pintype "passive"))
      (node (ref "RESET") (pin "1") (pinfunction "S_1") (pintype "passive"))
      (node (ref "RESET") (pin "2") (pinfunction "S1_2") (pintype "passive"))
      (node (ref "U$1") (pin "38") (pinfunction "~{RST}_38") (pintype "bidirectional"))
    )
    (net (code "32") (name "Net-(S1-1)") (class "Default")
      (node (ref "D1") (pin "A") (pinfunction "A_A") (pintype "passive"))
      (node (ref "S1") (pin "S1") (pinfunction "1_S1") (pintype "passive"))
    )
    (net (code "33") (name "Net-(S2-1)") (class "Default")
      (node (ref "D2") (pin "A") (pinfunction "A_A") (pintype "passive"))
      (node (ref "S2") (pin "S1") (pinfunction "1_S1") (pintype "passive"))
    )
    (net (code "34") (name "Net-(S5-1)") (class "Default")
      (node (ref "D5") (pin "A") (pinfunction "A_A") (pintype "passive"))
      (node (ref "S5") (pin "S1") (pinfunction "1_S1") (pintype "passive"))
    )
    (net (code "35") (name "Net-(S6-1)") (class "Default")
      (node (ref "D6") (pin "A") (pinfunction "A_A") (pintype "passive"))
      (node (ref "S6") (pin "S1") (pinfunction "1_S1") (pintype "passive"))
    )
    (net (code "36") (name "Net-(S7-1)") (class "Default")
      (node (ref "D7") (pin "A") (pinfunction "A_A") (pintype "passive"))
      (node (ref "S7") (pin "S1") (pinfunction "1_S1") (pintype "passive"))
    )
    (net (code "37") (name "Net-(S8-1)") (class "Default")
      (node (ref "D8") (pin "A") (pinfunction "A_A") (pintype "passive"))
      (node (ref "S8") (pin "S1") (pinfunction "1_S1") (pintype "passive"))
    )
    (net (code "38") (name "Net-(S9-1)") (class "Default")
      (node (ref "D9") (pin "A") (pinfunction "A_A") (pintype "passive"))
      (node (ref "S9") (pin "S1") (pinfunction "1_S1") (pintype "passive"))
    )
    (net (code "39") (name "Net-(S10-1)") (class "Default")
      (node (ref "D10") (pin "A") (pinfunction "A_A") (pintype "passive"))
      (node (ref "S10") (pin "S1") (pinfunction "1_S1") (pintype "passive"))
    )
    (net (code "40") (name "Net-(S11-1)") (class "Default")
      (node (ref "D11") (pin "A") (pinfunction "A_A") (pintype "passive"))
      (node (ref "S11") (pin "S1") (pinfunction "1_S1") (pintype "passive"))
    )
    (net (code "41") (name "Net-(S12-1)") (class "Default")
      (node (ref "D12") (pin "A") (pinfunction "A_A") (pintype "passive"))
      (node (ref "S12") (pin "S1") (pinfunction "1_S1") (pintype "passive"))
    )
    (net (code "42") (name "Net-(S13-1)") (class "Default")
      (node (ref "D13") (pin "A") (pinfunction "A_A") (pintype "passive"))
      (node (ref "S13") (pin "S1") (pinfunction "1_S1") (pintype "passive"))
    )
    (net (code "43") (name "Net-(S14-1)") (class "Default")
      (node (ref "D14") (pin "A") (pinfunction "A_A") (pintype "passive"))
      (node (ref "S14") (pin "S1") (pinfunction "1_S1") (pintype "passive"))
    )
    (net (code "44") (name "Net-(S15-1)") (class "Default")
      (node (ref "D15") (pin "A") (pinfunction "A_A") (pintype "passive"))
      (node (ref "S15") (pin "S1") (pinfunction "1_S1") (pintype "passive"))
    )
    (net (code "45") (name "Net-(S16-1)") (class "Default")
      (node (ref "D16") (pin "A") (pinfunction "A_A") (pintype "passive"))
      (node (ref "S16") (pin "S1") (pinfunction "1_S1") (pintype "passive"))
    )
    (net (code "46") (name "Net-(S17-1)") (class "Default")
      (node (ref "D17") (pin "A") (pinfunction "A_A") (pintype "passive"))
      (node (ref "S17") (pin "S1") (pinfunction "1_S1") (pintype "passive"))
    )
    (net (code "47") (name "Net-(S18-1)") (class "Default")
      (node (ref "D18") (pin "A") (pinfunction "A_A") (pintype "passive"))
      (node (ref "S18") (pin "S1") (pinfunction "1_S1") (pintype "passive"))
    )
    (net (code "48") (name "Net-(S19-1)") (class "Default")
      (node (ref "D19") (pin "A") (pinfunction "A_A") (pintype "passive"))
      (node (ref "S19") (pin "S1") (pinfunction "1_S1") (pintype "passive"))
    )
    (net (code "49") (name "Net-(S20-1)") (class "Default")
      (node (ref "D20") (pin "A") (pinfunction "A_A") (pintype "passive"))
      (node (ref "S20") (pin "S1") (pinfunction "1_S1") (pintype "passive"))
    )
    (net (code "50") (name "Net-(S21-1)") (class "Default")
      (node (ref "D21") (pin "A") (pinfunction "A_A") (pintype "passive"))
      (node (ref "S21") (pin "S1") (pinfunction "1_S1") (pintype "passive"))
    )
    (net (code "51") (name "Net-(S22-1)") (class "Default")
      (node (ref "D22") (pin "A") (pinfunction "A_A") (pintype "passive"))
      (node (ref "S22") (pin "S1") (pinfunction "1_S1") (pintype "passive"))
    )
    (net (code "52") (name "Net-(S23-1)") (class "Default")
      (node (ref "D23") (pin "A") (pinfunction "A_A") (pintype "passive"))
      (node (ref "S23") (pin "S1") (pinfunction "1_S1") (pintype "passive"))
    )
    (net (code "53") (name "Net-(S24-1)") (class "Default")
      (node (ref "D24") (pin "A") (pinfunction "A_A") (pintype "passive"))
      (node (ref "S24") (pin "S1") (pinfunction "1_S1") (pintype "passive"))
    )
    (net (code "54") (name "Net-(U$1F-PF3)") (class "Default")
      (node (ref "JP4") (pin "2") (pinfunction "2_2") (pintype "passive"))
      (node (ref "U$1") (pin "31") (pinfunction "PF3_31") (pintype "bidirectional"))
    )
    (net (code "55") (name "Net-(U$1G-OSC0)") (class "Default")
      (node (ref "C12") (pin "1") (pinfunction "1_1") (pintype "passive"))
      (node (ref "U$1") (pin "40") (pinfunction "OSC0_40") (pintype "bidirectional"))
      (node (ref "U$2") (pin "OSC0") (pinfunction "P$1_OSC0") (pintype "bidirectional"))
    )
    (net (code "56") (name "Net-(U$1G-OSC1)") (class "Default")
      (node (ref "C11") (pin "1") (pinfunction "1_1") (pintype "passive"))
      (node (ref "U$1") (pin "41") (pinfunction "OSC1_41") (pintype "bidirectional"))
      (node (ref "U$2") (pin "OSC1") (pinfunction "P$2_OSC1") (pintype "bidirectional"))
    )
    (net (code "57") (name "Net-(U$1G-~{WAKE})") (class "Default")
      (node (ref "R4") (pin "2") (pinfunction "2_2") (pintype "passive"))
      (node (ref "U$1") (pin "32") (pinfunction "~{WAKE}_32") (pintype "bidirectional"))
    )
    (net (code "58") (name "unconnected-(JP4-Pad1)") (class "Default")
      (node (ref "JP4") (pin "1") (pinfunction "1_1") (pintype "passive"))
    )
    (net (code "59") (name "unconnected-(U$1A-PA0-Pad17)") (class "Default")
      (node (ref "U$1") (pin "17") (pinfunction "PA0_17") (pintype "bidirectional"))
    )
    (net (code "60") (name "unconnected-(U$1A-PA1-Pad18)") (class "Default")
      (node (ref "U$1") (pin "18") (pinfunction "PA1_18") (pintype "bidirectional"))
    )
    (net (code "61") (name "unconnected-(U$1B-PB6-Pad1)") (class "Default")
      (node (ref "U$1") (pin "1") (pinfunction "PB6_1") (pintype "bidirectional"))
    )
    (net (code "62") (name "unconnected-(U$1B-PB7-Pad4)") (class "Default")
      (node (ref "U$1") (pin "4") (pinfunction "PB7_4") (pintype "bidirectional"))
    )
    (net (code "63") (name "unconnected-(U$1D-PD0-Pad61)") (class "Default")
      (node (ref "U$1") (pin "61") (pinfunction "PD0_61") (pintype "bidirectional"))
    )
    (net (code "64") (name "unconnected-(U$1D-PD1-Pad62)") (class "Default")
      (node (ref "U$1") (pin "62") (pinfunction "PD1_62") (pintype "bidirectional"))
    )
    (net (code "65") (name "unconnected-(U$1D-PD2-Pad63)") (class "Default")
      (node (ref "U$1") (pin "63") (pinfunction "PD2_63") (pintype "bidirectional"))
    )
    (net (code "66") (name "unconnected-(U$1D-PD3-Pad64)") (class "Default")
      (node (ref "U$1") (pin "64") (pinfunction "PD3_64") (pintype "bidirectional"))
    )
    (net (code "67") (name "unconnected-(U$1D-PD6-Pad53)") (class "Default")
      (node (ref "U$1") (pin "53") (pinfunction "PD6_53") (pintype "bidirectional"))
    )
    (net (code "68") (name "unconnected-(U$1F-PF4-Pad5)") (class "Default")
      (node (ref "U$1") (pin "5") (pinfunction "PF4_5") (pintype "bidirectional"))
    )
    (net (code "69") (name "unconnected-(U$1G-XOSC1-Pad36)") (class "Default")
      (node (ref "U$1") (pin "36") (pinfunction "XOSC1_36") (pintype "bidirectional"))
    )
    (net (code "70") (name "unconnected-(U$1G-~{HIB}-Pad33)") (class "Default")
      (node (ref "U$1") (pin "33") (pinfunction "~{HIB}_33") (pintype "bidirectional"))
    )
    (net (code "71") (name "unconnected-(U1-PadMH1)") (class "Default")
      (node (ref "U1") (pin "MH1") (pinfunction "MH1_MH1") (pintype "bidirectional"))
    )
    (net (code "72") (name "unconnected-(U1-PadMH2)") (class "Default")
      (node (ref "U1") (pin "MH2") (pinfunction "MH2_MH2") (pintype "bidirectional"))
    )
  )
)
